# smartwatch.net
KiCad netlist of a schematic drawn in Altium Designer
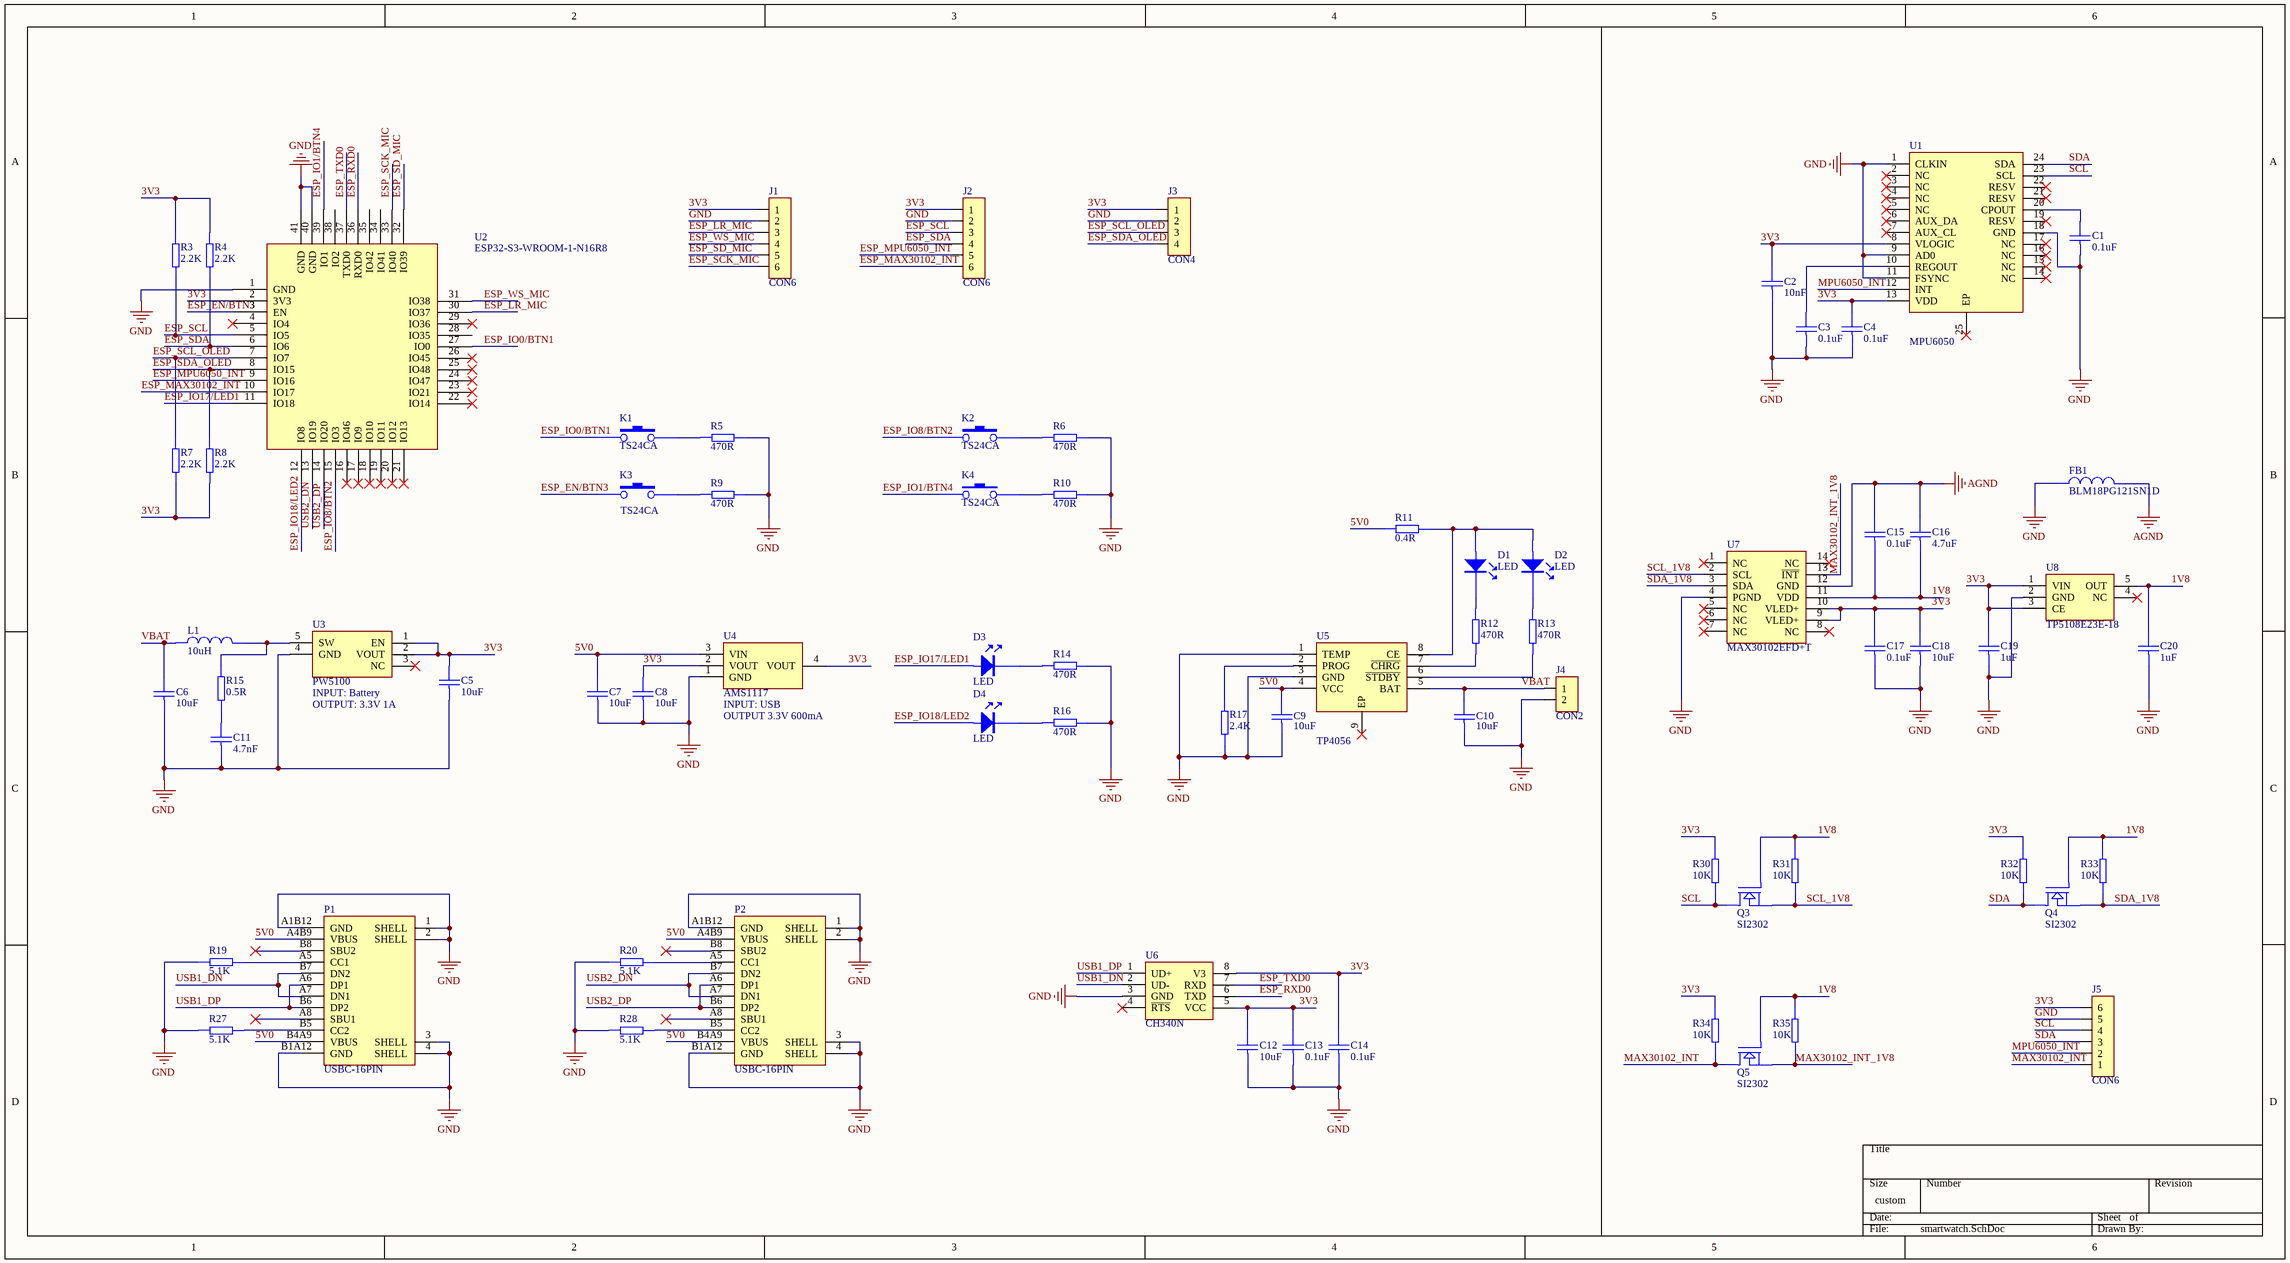
[diagram p0: smartwatch.SchDoc]

(export (version "E")
  (design (tool "Eeschema 10.0.6"))
  (components
    (comp (ref "C1")
      (value "0.1uF")
      (footprint "0603")
      (description "电容")
      (libsource (lib "smartwatch") (part "C"))
    )
    (comp (ref "C2")
      (value "10nF")
      (footprint "0603")
      (description "电容")
      (libsource (lib "smartwatch") (part "C"))
    )
    (comp (ref "C3")
      (value "0.1uF")
      (footprint "0603")
      (description "电容")
      (libsource (lib "smartwatch") (part "C"))
    )
    (comp (ref "C4")
      (value "0.1uF")
      (footprint "0603")
      (description "电容")
      (libsource (lib "smartwatch") (part "C"))
    )
    (comp (ref "C5")
      (value "10uF")
      (footprint "0603")
      (description "电容")
      (libsource (lib "smartwatch") (part "C"))
    )
    (comp (ref "C6")
      (value "10uF")
      (footprint "0603")
      (description "电容")
      (libsource (lib "smartwatch") (part "C"))
    )
    (comp (ref "C7")
      (value "10uF")
      (footprint "0603")
      (description "电容")
      (libsource (lib "smartwatch") (part "C"))
    )
    (comp (ref "C8")
      (value "10uF")
      (footprint "0603")
      (description "电容")
      (libsource (lib "smartwatch") (part "C"))
    )
    (comp (ref "C9")
      (value "10uF")
      (footprint "0603")
      (description "电容")
      (libsource (lib "smartwatch") (part "C"))
    )
    (comp (ref "C10")
      (value "10uF")
      (footprint "0603")
      (description "电容")
      (libsource (lib "smartwatch") (part "C"))
    )
    (comp (ref "C11")
      (value "4.7nF")
      (footprint "0603")
      (description "电容")
      (libsource (lib "smartwatch") (part "C"))
    )
    (comp (ref "C12")
      (value "10uF")
      (footprint "0603")
      (description "电容")
      (libsource (lib "smartwatch") (part "C"))
    )
    (comp (ref "C13")
      (value "0.1uF")
      (footprint "0603")
      (description "电容")
      (libsource (lib "smartwatch") (part "C"))
    )
    (comp (ref "C14")
      (value "0.1uF")
      (footprint "0603")
      (description "电容")
      (libsource (lib "smartwatch") (part "C"))
    )
    (comp (ref "C15")
      (value "0.1uF")
      (footprint "0603")
      (description "电容")
      (libsource (lib "smartwatch") (part "C"))
    )
    (comp (ref "C16")
      (value "4.7uF")
      (footprint "0603")
      (description "电容")
      (libsource (lib "smartwatch") (part "C"))
    )
    (comp (ref "C17")
      (value "0.1uF")
      (footprint "0603")
      (description "电容")
      (libsource (lib "smartwatch") (part "C"))
    )
    (comp (ref "C18")
      (value "10uF")
      (footprint "0603")
      (description "电容")
      (libsource (lib "smartwatch") (part "C"))
    )
    (comp (ref "C19")
      (value "1uF")
      (footprint "0603")
      (description "电容")
      (libsource (lib "smartwatch") (part "C"))
    )
    (comp (ref "C20")
      (value "1uF")
      (footprint "0603")
      (description "电容")
      (libsource (lib "smartwatch") (part "C"))
    )
    (comp (ref "D1") (value "LED") (footprint "LED0805-R-RD") (libsource (lib "smartwatch") (part "LED")))
    (comp (ref "D2") (value "LED") (footprint "LED0805-R-RD") (libsource (lib "smartwatch") (part "LED")))
    (comp (ref "D3") (value "LED") (footprint "LED0805-R-RD") (libsource (lib "smartwatch") (part "LED")))
    (comp (ref "D4") (value "LED") (footprint "LED0805-R-RD") (libsource (lib "smartwatch") (part "LED")))
    (comp (ref "FB1")
      (value "BLM18PG121SN1D")
      (footprint "0603")
      (description "磁珠")
      (libsource (lib "smartwatch") (part "FB"))
    )
    (comp (ref "J1")
      (value "CON6")
      (footprint "FPC-SMD_P0.50-6P_AFC01-S06FCA-00")
      (libsource (lib "smartwatch") (part "CON6"))
    )
    (comp (ref "J2")
      (value "CON6")
      (footprint "FPC-SMD_P0.50-6P_AFC01-S06FCA-00")
      (libsource (lib "smartwatch") (part "CON6"))
    )
    (comp (ref "J3")
      (value "CON4")
      (footprint "HDR2.54-M-LI-4P")
      (libsource (lib "smartwatch") (part "CON4"))
    )
    (comp (ref "J4") (value "CON2") (footprint "SIP-1.25-2P") (libsource (lib "smartwatch") (part "CON2")))
    (comp (ref "J5")
      (value "CON6")
      (footprint "FPC-SMD_P0.50-6P_AFC01-S06FCA-00")
      (libsource (lib "") (part "CON6_1"))
    )
    (comp (ref "K1")
      (value "TS24CA")
      (footprint "SW-SMD_TS24CA")
      (description "4.55*1.8*3.5mm 卧贴 轻触开关")
      (libsource (lib "smartwatch") (part "TS24CA"))
    )
    (comp (ref "K2")
      (value "TS24CA")
      (footprint "SW-SMD_TS24CA")
      (description "4.55*1.8*3.5mm 卧贴 轻触开关")
      (libsource (lib "smartwatch") (part "TS24CA"))
    )
    (comp (ref "K3")
      (value "TS24CA")
      (footprint "SW-SMD_TS24CA")
      (description "4.55*1.8*3.5mm 卧贴 轻触开关")
      (libsource (lib "smartwatch") (part "TS24CA"))
    )
    (comp (ref "K4")
      (value "TS24CA")
      (footprint "SW-SMD_TS24CA")
      (description "4.55*1.8*3.5mm 卧贴 轻触开关")
      (libsource (lib "smartwatch") (part "TS24CA"))
    )
    (comp (ref "L1")
      (value "10uH")
      (footprint "IND-SMD_L5.4-W5.2_FXL0530")
      (description "电感")
      (libsource (lib "smartwatch") (part "L"))
    )
    (comp (ref "P1")
      (value "USBC-16PIN")
      (footprint "USB-C-SMD_G-SWITCH_GT-USB-7010ASV")
      (description "USB Type-C母座 16PIN 卧贴")
      (libsource (lib "smartwatch") (part "USBC-16PIN"))
    )
    (comp (ref "P2")
      (value "USBC-16PIN")
      (footprint "USB-C-SMD_G-SWITCH_GT-USB-7010ASV")
      (description "USB Type-C母座 16PIN 卧贴")
      (libsource (lib "smartwatch") (part "USBC-16PIN"))
    )
    (comp (ref "Q3")
      (value "SI2302")
      (footprint "SOT-23-3_L2.9-W1.3-P1.90-LS2.4-BR")
      (libsource (lib "smartwatch") (part "MOSFET N"))
    )
    (comp (ref "Q4")
      (value "SI2302")
      (footprint "SOT-23-3_L2.9-W1.3-P1.90-LS2.4-BR")
      (libsource (lib "smartwatch") (part "MOSFET N"))
    )
    (comp (ref "Q5")
      (value "SI2302")
      (footprint "SOT-23-3_L2.9-W1.3-P1.90-LS2.4-BR")
      (libsource (lib "smartwatch") (part "MOSFET N"))
    )
    (comp (ref "R3")
      (value "2.2K")
      (footprint "0603")
      (description "电阻")
      (libsource (lib "smartwatch") (part "R"))
    )
    (comp (ref "R4")
      (value "2.2K")
      (footprint "0603")
      (description "电阻")
      (libsource (lib "smartwatch") (part "R"))
    )
    (comp (ref "R5")
      (value "470R")
      (footprint "0603")
      (description "电阻")
      (libsource (lib "smartwatch") (part "R"))
    )
    (comp (ref "R6")
      (value "470R")
      (footprint "0603")
      (description "电阻")
      (libsource (lib "smartwatch") (part "R"))
    )
    (comp (ref "R7")
      (value "2.2K")
      (footprint "0603")
      (description "电阻")
      (libsource (lib "smartwatch") (part "R"))
    )
    (comp (ref "R8")
      (value "2.2K")
      (footprint "0603")
      (description "电阻")
      (libsource (lib "smartwatch") (part "R"))
    )
    (comp (ref "R9")
      (value "470R")
      (footprint "0603")
      (description "电阻")
      (libsource (lib "smartwatch") (part "R"))
    )
    (comp (ref "R10")
      (value "470R")
      (footprint "0603")
      (description "电阻")
      (libsource (lib "smartwatch") (part "R"))
    )
    (comp (ref "R11")
      (value "0.4R")
      (footprint "2512")
      (description "电阻")
      (libsource (lib "smartwatch") (part "R"))
    )
    (comp (ref "R12")
      (value "470R")
      (footprint "0603")
      (description "电阻")
      (libsource (lib "smartwatch") (part "R"))
    )
    (comp (ref "R13")
      (value "470R")
      (footprint "0603")
      (description "电阻")
      (libsource (lib "smartwatch") (part "R"))
    )
    (comp (ref "R14")
      (value "470R")
      (footprint "0603")
      (description "电阻")
      (libsource (lib "smartwatch") (part "R"))
    )
    (comp (ref "R15")
      (value "0.5R")
      (footprint "0603")
      (description "电阻")
      (libsource (lib "smartwatch") (part "R"))
    )
    (comp (ref "R16")
      (value "470R")
      (footprint "0603")
      (description "电阻")
      (libsource (lib "smartwatch") (part "R"))
    )
    (comp (ref "R17")
      (value "2.4K")
      (footprint "0603")
      (description "电阻")
      (libsource (lib "smartwatch") (part "R"))
    )
    (comp (ref "R19")
      (value "5.1K")
      (footprint "0603")
      (description "电阻")
      (libsource (lib "smartwatch") (part "R"))
    )
    (comp (ref "R20")
      (value "5.1K")
      (footprint "0603")
      (description "电阻")
      (libsource (lib "smartwatch") (part "R"))
    )
    (comp (ref "R27")
      (value "5.1K")
      (footprint "0603")
      (description "电阻")
      (libsource (lib "smartwatch") (part "R"))
    )
    (comp (ref "R28")
      (value "5.1K")
      (footprint "0603")
      (description "电阻")
      (libsource (lib "smartwatch") (part "R"))
    )
    (comp (ref "R30")
      (value "10K")
      (footprint "0603")
      (description "电阻")
      (libsource (lib "smartwatch") (part "R"))
    )
    (comp (ref "R31")
      (value "10K")
      (footprint "0603")
      (description "电阻")
      (libsource (lib "smartwatch") (part "R"))
    )
    (comp (ref "R32")
      (value "10K")
      (footprint "0603")
      (description "电阻")
      (libsource (lib "smartwatch") (part "R"))
    )
    (comp (ref "R33")
      (value "10K")
      (footprint "0603")
      (description "电阻")
      (libsource (lib "smartwatch") (part "R"))
    )
    (comp (ref "R34")
      (value "10K")
      (footprint "0603")
      (description "电阻")
      (libsource (lib "smartwatch") (part "R"))
    )
    (comp (ref "R35")
      (value "10K")
      (footprint "0603")
      (description "电阻")
      (libsource (lib "smartwatch") (part "R"))
    )
    (comp (ref "U1")
      (value "MPU6050")
      (footprint "QFN-24_L4.0-W4.0-P0.50-BL-EP2.7")
      (description "三轴加速度计和三轴陀螺仪，工作电压：2.375V~3.46V")
      (libsource (lib "smartwatch") (part "MPU6050"))
    )
    (comp (ref "U2")
      (value "ESP32-S3-WROOM-1-N16R8")
      (footprint "WIRELM-SMD_ESP32-S3-WROOM-1_reduced")
      (description "通用型Wi-Fi+低功耗蓝牙MCU模组")
      (libsource (lib "smartwatch") (part "ESP32-S3-WROOM-1-N16R8"))
    )
    (comp (ref "U3")
      (value "PW5100")
      (footprint "SOT95P280X125-5N")
      (description "DC-DC")
      (libsource (lib "smartwatch") (part "PW5100"))
    )
    (comp (ref "U4")
      (value "AMS1117")
      (footprint "SOT223")
      (description "LDO 线性稳压器")
      (libsource (lib "smartwatch") (part "AMS1117"))
    )
    (comp (ref "U5")
      (value "TP4056")
      (footprint "ESOP-8_L4.9-W3.9-P1.27-LS6.0-BL-EP")
      (description "1A线性锂离子电池充电器")
      (libsource (lib "smartwatch") (part "TP4056"))
    )
    (comp (ref "U6")
      (value "CH340N")
      (footprint "SOP-8_L4.9-W3.9-P1.27-LS6.0-BL")
      (description "USB2.0芯片CH340N")
      (libsource (lib "smartwatch") (part "CH340N"))
    )
    (comp (ref "U7")
      (value "MAX30102EFD+T")
      (footprint "OESIP-14_L5.6-W3.3-P0.80-TL")
      (description "高灵敏度脉搏血氧仪和心率传感器")
      (libsource (lib "smartwatch") (part "MAX30102EFD+T"))
    )
    (comp (ref "U8")
      (value "TP5108E23E-18")
      (footprint "SOT-23-5_L3.0-W1.7-P0.95-LS2.8-BL")
      (description "LDO 输出1.8V 500mA")
      (libsource (lib "smartwatch") (part "TP5108E23E-18"))
    )
  )
  (nets
    (net (code "1") (name "/1V8") (class "Default")
      (node (ref "C15") (pin "1") (pinfunction "1_1") (pintype "passive"))
      (node (ref "C16") (pin "1") (pinfunction "1_1") (pintype "passive"))
      (node (ref "C20") (pin "2") (pinfunction "2_2") (pintype "passive"))
      (node (ref "Q3") (pin "1") (pinfunction "G_1") (pintype "passive"))
      (node (ref "Q4") (pin "1") (pinfunction "G_1") (pintype "passive"))
      (node (ref "Q5") (pin "1") (pinfunction "G_1") (pintype "passive"))
      (node (ref "R31") (pin "2") (pinfunction "2_2") (pintype "passive"))
      (node (ref "R33") (pin "2") (pinfunction "2_2") (pintype "passive"))
      (node (ref "R35") (pin "2") (pinfunction "2_2") (pintype "passive"))
      (node (ref "U7") (pin "11") (pinfunction "VDD_11") (pintype "passive"))
      (node (ref "U8") (pin "5") (pinfunction "OUT_5") (pintype "passive"))
    )
    (net (code "2") (name "/3V3") (class "Default")
      (node (ref "C12") (pin "2") (pinfunction "2_2") (pintype "passive"))
      (node (ref "C13") (pin "2") (pinfunction "2_2") (pintype "passive"))
      (node (ref "C14") (pin "2") (pinfunction "2_2") (pintype "passive"))
      (node (ref "C17") (pin "2") (pinfunction "2_2") (pintype "passive"))
      (node (ref "C18") (pin "2") (pinfunction "2_2") (pintype "passive"))
      (node (ref "C19") (pin "2") (pinfunction "2_2") (pintype "passive"))
      (node (ref "C2") (pin "2") (pinfunction "2_2") (pintype "passive"))
      (node (ref "C4") (pin "2") (pinfunction "2_2") (pintype "passive"))
      (node (ref "C5") (pin "2") (pinfunction "2_2") (pintype "passive"))
      (node (ref "C8") (pin "2") (pinfunction "2_2") (pintype "passive"))
      (node (ref "J1") (pin "1") (pinfunction "1_1") (pintype "passive"))
      (node (ref "J2") (pin "1") (pinfunction "1_1") (pintype "passive"))
      (node (ref "J3") (pin "1") (pinfunction "1_1") (pintype "passive"))
      (node (ref "J5") (pin "6") (pinfunction "6_6") (pintype "passive"))
      (node (ref "R3") (pin "2") (pinfunction "2_2") (pintype "passive"))
      (node (ref "R30") (pin "2") (pinfunction "2_2") (pintype "passive"))
      (node (ref "R32") (pin "2") (pinfunction "2_2") (pintype "passive"))
      (node (ref "R34") (pin "2") (pinfunction "2_2") (pintype "passive"))
      (node (ref "R4") (pin "2") (pinfunction "2_2") (pintype "passive"))
      (node (ref "R7") (pin "1") (pinfunction "1_1") (pintype "passive"))
      (node (ref "R8") (pin "1") (pinfunction "1_1") (pintype "passive"))
      (node (ref "U1") (pin "13") (pinfunction "VDD_13") (pintype "passive"))
      (node (ref "U1") (pin "8") (pinfunction "VLOGIC_8") (pintype "passive"))
      (node (ref "U2") (pin "2") (pinfunction "3V3_2") (pintype "passive"))
      (node (ref "U3") (pin "1") (pinfunction "EN_1") (pintype "passive"))
      (node (ref "U3") (pin "2") (pinfunction "VOUT_2") (pintype "passive"))
      (node (ref "U4") (pin "2") (pinfunction "VOUT_2") (pintype "passive"))
      (node (ref "U4") (pin "4") (pinfunction "VOUT_4") (pintype "passive"))
      (node (ref "U6") (pin "5") (pinfunction "VCC_5") (pintype "passive"))
      (node (ref "U6") (pin "8") (pinfunction "V3_8") (pintype "passive"))
      (node (ref "U7") (pin "10") (pinfunction "VLED+_10") (pintype "passive"))
      (node (ref "U7") (pin "9") (pinfunction "VLED+_9") (pintype "passive"))
      (node (ref "U8") (pin "1") (pinfunction "VIN_1") (pintype "passive"))
      (node (ref "U8") (pin "3") (pinfunction "CE_3") (pintype "passive"))
    )
    (net (code "3") (name "/5V0") (class "Default")
      (node (ref "C7") (pin "2") (pinfunction "2_2") (pintype "passive"))
      (node (ref "C9") (pin "2") (pinfunction "2_2") (pintype "passive"))
      (node (ref "P1") (pin "A4B9") (pinfunction "VBUS_A4B9") (pintype "passive"))
      (node (ref "P1") (pin "B4A9") (pinfunction "VBUS_B4A9") (pintype "passive"))
      (node (ref "P2") (pin "A4B9") (pinfunction "VBUS_A4B9") (pintype "passive"))
      (node (ref "P2") (pin "B4A9") (pinfunction "VBUS_B4A9") (pintype "passive"))
      (node (ref "R11") (pin "2") (pinfunction "2_2") (pintype "passive"))
      (node (ref "U4") (pin "3") (pinfunction "VIN_3") (pintype "passive"))
      (node (ref "U5") (pin "4") (pinfunction "VCC_4") (pintype "passive"))
    )
    (net (code "4") (name "/ESP_EN{slash}BTN3") (class "Default")
      (node (ref "K3") (pin "1") (pinfunction "1_1") (pintype "passive"))
      (node (ref "U2") (pin "3") (pinfunction "EN_3") (pintype "passive"))
    )
    (net (code "5") (name "/ESP_IO0{slash}BTN1") (class "Default")
      (node (ref "K1") (pin "1") (pinfunction "1_1") (pintype "passive"))
      (node (ref "U2") (pin "27") (pinfunction "IO0_27") (pintype "passive"))
    )
    (net (code "6") (name "/ESP_IO1{slash}BTN4") (class "Default")
      (node (ref "K4") (pin "2") (pinfunction "2_2") (pintype "passive"))
      (node (ref "U2") (pin "39") (pinfunction "IO1_39") (pintype "passive"))
    )
    (net (code "7") (name "/ESP_IO8{slash}BTN2") (class "Default")
      (node (ref "K2") (pin "1") (pinfunction "1_1") (pintype "passive"))
      (node (ref "U2") (pin "15") (pinfunction "IO3_15") (pintype "passive"))
    )
    (net (code "8") (name "/ESP_IO17{slash}LED1") (class "Default")
      (node (ref "D3") (pin "1") (pinfunction "1_1") (pintype "passive"))
      (node (ref "U2") (pin "11") (pinfunction "IO18_11") (pintype "passive"))
    )
    (net (code "9") (name "/ESP_IO18{slash}LED2") (class "Default")
      (node (ref "D4") (pin "1") (pinfunction "1_1") (pintype "passive"))
      (node (ref "U2") (pin "12") (pinfunction "IO8_12") (pintype "passive"))
    )
    (net (code "10") (name "/ESP_LR_MIC") (class "Default")
      (node (ref "J1") (pin "3") (pinfunction "3_3") (pintype "passive"))
      (node (ref "U2") (pin "30") (pinfunction "IO37_30") (pintype "passive"))
    )
    (net (code "11") (name "/ESP_MAX30102_INT") (class "Default")
      (node (ref "J2") (pin "6") (pinfunction "6_6") (pintype "passive"))
      (node (ref "U2") (pin "10") (pinfunction "IO17_10") (pintype "passive"))
    )
    (net (code "12") (name "/ESP_MPU6050_INT") (class "Default")
      (node (ref "J2") (pin "5") (pinfunction "5_5") (pintype "passive"))
      (node (ref "U2") (pin "9") (pinfunction "IO16_9") (pintype "passive"))
    )
    (net (code "13") (name "/ESP_RXD0") (class "Default")
      (node (ref "U2") (pin "36") (pinfunction "RXD0_36") (pintype "passive"))
      (node (ref "U6") (pin "6") (pinfunction "TXD_6") (pintype "passive"))
    )
    (net (code "14") (name "/ESP_SCK_MIC") (class "Default")
      (node (ref "J1") (pin "6") (pinfunction "6_6") (pintype "passive"))
      (node (ref "U2") (pin "33") (pinfunction "IO40_33") (pintype "passive"))
    )
    (net (code "15") (name "/ESP_SCL") (class "Default")
      (node (ref "J2") (pin "3") (pinfunction "3_3") (pintype "passive"))
      (node (ref "R3") (pin "1") (pinfunction "1_1") (pintype "passive"))
      (node (ref "U2") (pin "5") (pinfunction "IO5_5") (pintype "passive"))
    )
    (net (code "16") (name "/ESP_SCL_OLED") (class "Default")
      (node (ref "J3") (pin "3") (pinfunction "3_3") (pintype "passive"))
      (node (ref "R7") (pin "2") (pinfunction "2_2") (pintype "passive"))
      (node (ref "U2") (pin "7") (pinfunction "IO7_7") (pintype "passive"))
    )
    (net (code "17") (name "/ESP_SDA") (class "Default")
      (node (ref "J2") (pin "4") (pinfunction "4_4") (pintype "passive"))
      (node (ref "R4") (pin "1") (pinfunction "1_1") (pintype "passive"))
      (node (ref "U2") (pin "6") (pinfunction "IO6_6") (pintype "passive"))
    )
    (net (code "18") (name "/ESP_SDA_OLED") (class "Default")
      (node (ref "J3") (pin "4") (pinfunction "4_4") (pintype "passive"))
      (node (ref "R8") (pin "2") (pinfunction "2_2") (pintype "passive"))
      (node (ref "U2") (pin "8") (pinfunction "IO15_8") (pintype "passive"))
    )
    (net (code "19") (name "/ESP_SD_MIC") (class "Default")
      (node (ref "J1") (pin "5") (pinfunction "5_5") (pintype "passive"))
      (node (ref "U2") (pin "32") (pinfunction "IO39_32") (pintype "passive"))
    )
    (net (code "20") (name "/ESP_TXD0") (class "Default")
      (node (ref "U2") (pin "37") (pinfunction "TXD0_37") (pintype "passive"))
      (node (ref "U6") (pin "7") (pinfunction "RXD_7") (pintype "passive"))
    )
    (net (code "21") (name "/ESP_WS_MIC") (class "Default")
      (node (ref "J1") (pin "4") (pinfunction "4_4") (pintype "passive"))
      (node (ref "U2") (pin "31") (pinfunction "IO38_31") (pintype "passive"))
    )
    (net (code "22") (name "/MAX30102_INT") (class "Default")
      (node (ref "J5") (pin "1") (pinfunction "1_1") (pintype "passive"))
      (node (ref "Q5") (pin "3") (pinfunction "D_3") (pintype "passive"))
      (node (ref "R34") (pin "1") (pinfunction "1_1") (pintype "passive"))
    )
    (net (code "23") (name "/MAX30102_INT_1V8") (class "Default")
      (node (ref "Q5") (pin "2") (pinfunction "S_2") (pintype "passive"))
      (node (ref "R35") (pin "1") (pinfunction "1_1") (pintype "passive"))
      (node (ref "U7") (pin "13") (pinfunction "~{INT}_13") (pintype "passive"))
    )
    (net (code "24") (name "/MPU6050_INT") (class "Default")
      (node (ref "J5") (pin "2") (pinfunction "2_2") (pintype "passive"))
      (node (ref "U1") (pin "12") (pinfunction "INT_12") (pintype "passive"))
    )
    (net (code "25") (name "/SCL") (class "Default")
      (node (ref "J5") (pin "4") (pinfunction "4_4") (pintype "passive"))
      (node (ref "Q3") (pin "3") (pinfunction "D_3") (pintype "passive"))
      (node (ref "R30") (pin "1") (pinfunction "1_1") (pintype "passive"))
      (node (ref "U1") (pin "23") (pinfunction "SCL_23") (pintype "passive"))
    )
    (net (code "26") (name "/SCL_1V8") (class "Default")
      (node (ref "Q3") (pin "2") (pinfunction "S_2") (pintype "passive"))
      (node (ref "R31") (pin "1") (pinfunction "1_1") (pintype "passive"))
      (node (ref "U7") (pin "2") (pinfunction "SCL_2") (pintype "passive"))
    )
    (net (code "27") (name "/SDA") (class "Default")
      (node (ref "J5") (pin "3") (pinfunction "3_3") (pintype "passive"))
      (node (ref "Q4") (pin "3") (pinfunction "D_3") (pintype "passive"))
      (node (ref "R32") (pin "1") (pinfunction "1_1") (pintype "passive"))
      (node (ref "U1") (pin "24") (pinfunction "SDA_24") (pintype "passive"))
    )
    (net (code "28") (name "/SDA_1V8") (class "Default")
      (node (ref "Q4") (pin "2") (pinfunction "S_2") (pintype "passive"))
      (node (ref "R33") (pin "1") (pinfunction "1_1") (pintype "passive"))
      (node (ref "U7") (pin "3") (pinfunction "SDA_3") (pintype "passive"))
    )
    (net (code "29") (name "/USB1_DN") (class "Default")
      (node (ref "P1") (pin "A7") (pinfunction "DN1_A7") (pintype "passive"))
      (node (ref "P1") (pin "B7") (pinfunction "DN2_B7") (pintype "passive"))
      (node (ref "U6") (pin "2") (pinfunction "UD-_2") (pintype "passive"))
    )
    (net (code "30") (name "/USB1_DP") (class "Default")
      (node (ref "P1") (pin "A6") (pinfunction "DP1_A6") (pintype "passive"))
      (node (ref "P1") (pin "B6") (pinfunction "DP2_B6") (pintype "passive"))
      (node (ref "U6") (pin "1") (pinfunction "UD+_1") (pintype "passive"))
    )
    (net (code "31") (name "/USB2_DN") (class "Default")
      (node (ref "P2") (pin "A7") (pinfunction "DN1_A7") (pintype "passive"))
      (node (ref "P2") (pin "B7") (pinfunction "DN2_B7") (pintype "passive"))
      (node (ref "U2") (pin "13") (pinfunction "IO19_13") (pintype "passive"))
    )
    (net (code "32") (name "/USB2_DP") (class "Default")
      (node (ref "P2") (pin "A6") (pinfunction "DP1_A6") (pintype "passive"))
      (node (ref "P2") (pin "B6") (pinfunction "DP2_B6") (pintype "passive"))
      (node (ref "U2") (pin "14") (pinfunction "IO20_14") (pintype "passive"))
    )
    (net (code "33") (name "/VBAT") (class "Default")
      (node (ref "C10") (pin "2") (pinfunction "2_2") (pintype "passive"))
      (node (ref "C6") (pin "2") (pinfunction "2_2") (pintype "passive"))
      (node (ref "J4") (pin "1") (pinfunction "1_1") (pintype "passive"))
      (node (ref "L1") (pin "1") (pinfunction "1_1") (pintype "passive"))
      (node (ref "U5") (pin "5") (pinfunction "BAT_5") (pintype "passive"))
    )
    (net (code "34") (name "AGND") (class "Default")
      (node (ref "C15") (pin "2") (pinfunction "2_2") (pintype "passive"))
      (node (ref "C16") (pin "2") (pinfunction "2_2") (pintype "passive"))
      (node (ref "FB1") (pin "2") (pinfunction "2_2") (pintype "passive"))
      (node (ref "U7") (pin "12") (pinfunction "GND_12") (pintype "passive"))
    )
    (net (code "35") (name "GND") (class "Default")
      (node (ref "C1") (pin "1") (pinfunction "1_1") (pintype "passive"))
      (node (ref "C10") (pin "1") (pinfunction "1_1") (pintype "passive"))
      (node (ref "C11") (pin "1") (pinfunction "1_1") (pintype "passive"))
      (node (ref "C12") (pin "1") (pinfunction "1_1") (pintype "passive"))
      (node (ref "C13") (pin "1") (pinfunction "1_1") (pintype "passive"))
      (node (ref "C14") (pin "1") (pinfunction "1_1") (pintype "passive"))
      (node (ref "C17") (pin "1") (pinfunction "1_1") (pintype "passive"))
      (node (ref "C18") (pin "1") (pinfunction "1_1") (pintype "passive"))
      (node (ref "C19") (pin "1") (pinfunction "1_1") (pintype "passive"))
      (node (ref "C2") (pin "1") (pinfunction "1_1") (pintype "passive"))
      (node (ref "C20") (pin "1") (pinfunction "1_1") (pintype "passive"))
      (node (ref "C3") (pin "1") (pinfunction "1_1") (pintype "passive"))
      (node (ref "C4") (pin "1") (pinfunction "1_1") (pintype "passive"))
      (node (ref "C5") (pin "1") (pinfunction "1_1") (pintype "passive"))
      (node (ref "C6") (pin "1") (pinfunction "1_1") (pintype "passive"))
      (node (ref "C7") (pin "1") (pinfunction "1_1") (pintype "passive"))
      (node (ref "C8") (pin "1") (pinfunction "1_1") (pintype "passive"))
      (node (ref "C9") (pin "1") (pinfunction "1_1") (pintype "passive"))
      (node (ref "FB1") (pin "1") (pinfunction "1_1") (pintype "passive"))
      (node (ref "J1") (pin "2") (pinfunction "2_2") (pintype "passive"))
      (node (ref "J2") (pin "2") (pinfunction "2_2") (pintype "passive"))
      (node (ref "J3") (pin "2") (pinfunction "2_2") (pintype "passive"))
      (node (ref "J4") (pin "2") (pinfunction "2_2") (pintype "passive"))
      (node (ref "J5") (pin "5") (pinfunction "5_5") (pintype "passive"))
      (node (ref "P1") (pin "1") (pinfunction "SHELL_1") (pintype "passive"))
      (node (ref "P1") (pin "2") (pinfunction "SHELL_2") (pintype "passive"))
      (node (ref "P1") (pin "3") (pinfunction "SHELL_3") (pintype "passive"))
      (node (ref "P1") (pin "4") (pinfunction "SHELL_4") (pintype "passive"))
      (node (ref "P1") (pin "A1B12") (pinfunction "GND_A1B12") (pintype "passive"))
      (node (ref "P1") (pin "B1A12") (pinfunction "GND_B1A12") (pintype "passive"))
      (node (ref "P2") (pin "1") (pinfunction "SHELL_1") (pintype "passive"))
      (node (ref "P2") (pin "2") (pinfunction "SHELL_2") (pintype "passive"))
      (node (ref "P2") (pin "3") (pinfunction "SHELL_3") (pintype "passive"))
      (node (ref "P2") (pin "4") (pinfunction "SHELL_4") (pintype "passive"))
      (node (ref "P2") (pin "A1B12") (pinfunction "GND_A1B12") (pintype "passive"))
      (node (ref "P2") (pin "B1A12") (pinfunction "GND_B1A12") (pintype "passive"))
      (node (ref "R10") (pin "2") (pinfunction "2_2") (pintype "passive"))
      (node (ref "R14") (pin "1") (pinfunction "1_1") (pintype "passive"))
      (node (ref "R16") (pin "1") (pinfunction "1_1") (pintype "passive"))
      (node (ref "R17") (pin "2") (pinfunction "2_2") (pintype "passive"))
      (node (ref "R19") (pin "1") (pinfunction "1_1") (pintype "passive"))
      (node (ref "R20") (pin "1") (pinfunction "1_1") (pintype "passive"))
      (node (ref "R27") (pin "1") (pinfunction "1_1") (pintype "passive"))
      (node (ref "R28") (pin "1") (pinfunction "1_1") (pintype "passive"))
      (node (ref "R5") (pin "2") (pinfunction "2_2") (pintype "passive"))
      (node (ref "R6") (pin "2") (pinfunction "2_2") (pintype "passive"))
      (node (ref "R9") (pin "2") (pinfunction "2_2") (pintype "passive"))
      (node (ref "U1") (pin "1") (pinfunction "CLKIN_1") (pintype "passive"))
      (node (ref "U1") (pin "11") (pinfunction "FSYNC_11") (pintype "passive"))
      (node (ref "U1") (pin "18") (pinfunction "GND_18") (pintype "passive"))
      (node (ref "U1") (pin "9") (pinfunction "AD0_9") (pintype "passive"))
      (node (ref "U2") (pin "1") (pinfunction "GND_1") (pintype "passive"))
      (node (ref "U2") (pin "40") (pinfunction "GND_40") (pintype "passive"))
      (node (ref "U2") (pin "41") (pinfunction "GND_41") (pintype "passive"))
      (node (ref "U3") (pin "4") (pinfunction "GND_4") (pintype "passive"))
      (node (ref "U4") (pin "1") (pinfunction "GND_1") (pintype "passive"))
      (node (ref "U5") (pin "1") (pinfunction "TEMP_1") (pintype "passive"))
      (node (ref "U5") (pin "3") (pinfunction "GND_3") (pintype "passive"))
      (node (ref "U6") (pin "3") (pinfunction "GND_3") (pintype "passive"))
      (node (ref "U7") (pin "4") (pinfunction "PGND_4") (pintype "passive"))
      (node (ref "U8") (pin "2") (pinfunction "GND_2") (pintype "passive"))
    )
    (net (code "36") (name "Net-(C11-Pad2)") (class "Default")
      (node (ref "C11") (pin "2") (pinfunction "2_2") (pintype "passive"))
      (node (ref "R15") (pin "1") (pinfunction "1_1") (pintype "passive"))
    )
    (net (code "37") (name "Net-(D1-Pad2)") (class "Default")
      (node (ref "D1") (pin "2") (pinfunction "2_2") (pintype "passive"))
      (node (ref "R12") (pin "2") (pinfunction "2_2") (pintype "passive"))
    )
    (net (code "38") (name "Net-(D2-Pad2)") (class "Default")
      (node (ref "D2") (pin "2") (pinfunction "2_2") (pintype "passive"))
      (node (ref "R13") (pin "2") (pinfunction "2_2") (pintype "passive"))
    )
    (net (code "39") (name "Net-(D3-Pad2)") (class "Default")
      (node (ref "D3") (pin "2") (pinfunction "2_2") (pintype "passive"))
      (node (ref "R14") (pin "2") (pinfunction "2_2") (pintype "passive"))
    )
    (net (code "40") (name "Net-(D4-Pad2)") (class "Default")
      (node (ref "D4") (pin "2") (pinfunction "2_2") (pintype "passive"))
      (node (ref "R16") (pin "2") (pinfunction "2_2") (pintype "passive"))
    )
    (net (code "41") (name "Net-(K1-Pad2)") (class "Default")
      (node (ref "K1") (pin "2") (pinfunction "2_2") (pintype "passive"))
      (node (ref "R5") (pin "1") (pinfunction "1_1") (pintype "passive"))
    )
    (net (code "42") (name "Net-(K2-Pad2)") (class "Default")
      (node (ref "K2") (pin "2") (pinfunction "2_2") (pintype "passive"))
      (node (ref "R6") (pin "1") (pinfunction "1_1") (pintype "passive"))
    )
    (net (code "43") (name "Net-(K3-Pad2)") (class "Default")
      (node (ref "K3") (pin "2") (pinfunction "2_2") (pintype "passive"))
      (node (ref "R9") (pin "1") (pinfunction "1_1") (pintype "passive"))
    )
    (net (code "44") (name "Net-(K4-Pad1)") (class "Default")
      (node (ref "K4") (pin "1") (pinfunction "1_1") (pintype "passive"))
      (node (ref "R10") (pin "1") (pinfunction "1_1") (pintype "passive"))
    )
    (net (code "45") (name "Net-(P1-CC1)") (class "Default")
      (node (ref "P1") (pin "A5") (pinfunction "CC1_A5") (pintype "passive"))
      (node (ref "R19") (pin "2") (pinfunction "2_2") (pintype "passive"))
    )
    (net (code "46") (name "Net-(P1-CC2)") (class "Default")
      (node (ref "P1") (pin "B5") (pinfunction "CC2_B5") (pintype "passive"))
      (node (ref "R27") (pin "2") (pinfunction "2_2") (pintype "passive"))
    )
    (net (code "47") (name "Net-(P2-CC1)") (class "Default")
      (node (ref "P2") (pin "A5") (pinfunction "CC1_A5") (pintype "passive"))
      (node (ref "R20") (pin "2") (pinfunction "2_2") (pintype "passive"))
    )
    (net (code "48") (name "Net-(P2-CC2)") (class "Default")
      (node (ref "P2") (pin "B5") (pinfunction "CC2_B5") (pintype "passive"))
      (node (ref "R28") (pin "2") (pinfunction "2_2") (pintype "passive"))
    )
    (net (code "49") (name "Net-(U1-CPOUT)") (class "Default")
      (node (ref "C1") (pin "2") (pinfunction "2_2") (pintype "passive"))
      (node (ref "U1") (pin "20") (pinfunction "CPOUT_20") (pintype "passive"))
    )
    (net (code "50") (name "Net-(U1-REGOUT)") (class "Default")
      (node (ref "C3") (pin "2") (pinfunction "2_2") (pintype "passive"))
      (node (ref "U1") (pin "10") (pinfunction "REGOUT_10") (pintype "passive"))
    )
    (net (code "51") (name "Net-(U3-SW)") (class "Default")
      (node (ref "L1") (pin "2") (pinfunction "2_2") (pintype "passive"))
      (node (ref "R15") (pin "2") (pinfunction "2_2") (pintype "passive"))
      (node (ref "U3") (pin "5") (pinfunction "SW_5") (pintype "passive"))
    )
    (net (code "52") (name "Net-(U5-CE)") (class "Default")
      (node (ref "D1") (pin "1") (pinfunction "1_1") (pintype "passive"))
      (node (ref "D2") (pin "1") (pinfunction "1_1") (pintype "passive"))
      (node (ref "R11") (pin "1") (pinfunction "1_1") (pintype "passive"))
      (node (ref "U5") (pin "8") (pinfunction "CE_8") (pintype "passive"))
    )
    (net (code "53") (name "Net-(U5-PROG)") (class "Default")
      (node (ref "R17") (pin "1") (pinfunction "1_1") (pintype "passive"))
      (node (ref "U5") (pin "2") (pinfunction "PROG_2") (pintype "passive"))
    )
    (net (code "54") (name "Net-(U5-~{CHRG})") (class "Default")
      (node (ref "R12") (pin "1") (pinfunction "1_1") (pintype "passive"))
      (node (ref "U5") (pin "7") (pinfunction "~{CHRG}_7") (pintype "passive"))
    )
    (net (code "55") (name "Net-(U5-~{STDBY})") (class "Default")
      (node (ref "R13") (pin "1") (pinfunction "1_1") (pintype "passive"))
      (node (ref "U5") (pin "6") (pinfunction "~{STDBY}_6") (pintype "passive"))
    )
    (net (code "56") (name "unconnected-(P1-SBU1-PadA8)") (class "Default")
      (node (ref "P1") (pin "A8") (pinfunction "SBU1_A8") (pintype "passive+no_connect"))
    )
    (net (code "57") (name "unconnected-(P1-SBU2-PadB8)") (class "Default")
      (node (ref "P1") (pin "B8") (pinfunction "SBU2_B8") (pintype "passive+no_connect"))
    )
    (net (code "58") (name "unconnected-(P2-SBU1-PadA8)") (class "Default")
      (node (ref "P2") (pin "A8") (pinfunction "SBU1_A8") (pintype "passive+no_connect"))
    )
    (net (code "59") (name "unconnected-(P2-SBU2-PadB8)") (class "Default")
      (node (ref "P2") (pin "B8") (pinfunction "SBU2_B8") (pintype "passive+no_connect"))
    )
    (net (code "60") (name "unconnected-(U1-AUX_CL-Pad7)") (class "Default")
      (node (ref "U1") (pin "7") (pinfunction "AUX_CL_7") (pintype "passive+no_connect"))
    )
    (net (code "61") (name "unconnected-(U1-AUX_DA-Pad6)") (class "Default")
      (node (ref "U1") (pin "6") (pinfunction "AUX_DA_6") (pintype "passive+no_connect"))
    )
    (net (code "62") (name "unconnected-(U1-EP-Pad25)") (class "Default")
      (node (ref "U1") (pin "25") (pinfunction "EP_25") (pintype "passive+no_connect"))
    )
    (net (code "63") (name "unconnected-(U1-NC-Pad2)") (class "Default")
      (node (ref "U1") (pin "2") (pinfunction "NC_2") (pintype "passive+no_connect"))
    )
    (net (code "64") (name "unconnected-(U1-NC-Pad3)") (class "Default")
      (node (ref "U1") (pin "3") (pinfunction "NC_3") (pintype "passive+no_connect"))
    )
    (net (code "65") (name "unconnected-(U1-NC-Pad4)") (class "Default")
      (node (ref "U1") (pin "4") (pinfunction "NC_4") (pintype "passive+no_connect"))
    )
    (net (code "66") (name "unconnected-(U1-NC-Pad5)") (class "Default")
      (node (ref "U1") (pin "5") (pinfunction "NC_5") (pintype "passive+no_connect"))
    )
    (net (code "67") (name "unconnected-(U1-NC-Pad14)") (class "Default")
      (node (ref "U1") (pin "14") (pinfunction "NC_14") (pintype "passive+no_connect"))
    )
    (net (code "68") (name "unconnected-(U1-NC-Pad15)") (class "Default")
      (node (ref "U1") (pin "15") (pinfunction "NC_15") (pintype "passive+no_connect"))
    )
    (net (code "69") (name "unconnected-(U1-NC-Pad16)") (class "Default")
      (node (ref "U1") (pin "16") (pinfunction "NC_16") (pintype "passive+no_connect"))
    )
    (net (code "70") (name "unconnected-(U1-NC-Pad17)") (class "Default")
      (node (ref "U1") (pin "17") (pinfunction "NC_17") (pintype "passive+no_connect"))
    )
    (net (code "71") (name "unconnected-(U1-RESV-Pad19)") (class "Default")
      (node (ref "U1") (pin "19") (pinfunction "RESV_19") (pintype "passive+no_connect"))
    )
    (net (code "72") (name "unconnected-(U1-RESV-Pad21)") (class "Default")
      (node (ref "U1") (pin "21") (pinfunction "RESV_21") (pintype "passive+no_connect"))
    )
    (net (code "73") (name "unconnected-(U1-RESV-Pad22)") (class "Default")
      (node (ref "U1") (pin "22") (pinfunction "RESV_22") (pintype "passive+no_connect"))
    )
    (net (code "74") (name "unconnected-(U2-IO2-Pad38)") (class "Default")
      (node (ref "U2") (pin "38") (pinfunction "IO2_38") (pintype "passive"))
    )
    (net (code "75") (name "unconnected-(U2-IO4-Pad4)") (class "Default")
      (node (ref "U2") (pin "4") (pinfunction "IO4_4") (pintype "passive+no_connect"))
    )
    (net (code "76") (name "unconnected-(U2-IO9-Pad17)") (class "Default")
      (node (ref "U2") (pin "17") (pinfunction "IO9_17") (pintype "passive+no_connect"))
    )
    (net (code "77") (name "unconnected-(U2-IO10-Pad18)") (class "Default")
      (node (ref "U2") (pin "18") (pinfunction "IO10_18") (pintype "passive+no_connect"))
    )
    (net (code "78") (name "unconnected-(U2-IO11-Pad19)") (class "Default")
      (node (ref "U2") (pin "19") (pinfunction "IO11_19") (pintype "passive+no_connect"))
    )
    (net (code "79") (name "unconnected-(U2-IO12-Pad20)") (class "Default")
      (node (ref "U2") (pin "20") (pinfunction "IO12_20") (pintype "passive+no_connect"))
    )
    (net (code "80") (name "unconnected-(U2-IO13-Pad21)") (class "Default")
      (node (ref "U2") (pin "21") (pinfunction "IO13_21") (pintype "passive+no_connect"))
    )
    (net (code "81") (name "unconnected-(U2-IO14-Pad22)") (class "Default")
      (node (ref "U2") (pin "22") (pinfunction "IO14_22") (pintype "passive+no_connect"))
    )
    (net (code "82") (name "unconnected-(U2-IO21-Pad23)") (class "Default")
      (node (ref "U2") (pin "23") (pinfunction "IO21_23") (pintype "passive+no_connect"))
    )
    (net (code "83") (name "unconnected-(U2-IO35-Pad28)") (class "Default")
      (node (ref "U2") (pin "28") (pinfunction "IO35_28") (pintype "passive"))
    )
    (net (code "84") (name "unconnected-(U2-IO36-Pad29)") (class "Default")
      (node (ref "U2") (pin "29") (pinfunction "IO36_29") (pintype "passive+no_connect"))
    )
    (net (code "85") (name "unconnected-(U2-IO41-Pad34)") (class "Default")
      (node (ref "U2") (pin "34") (pinfunction "IO41_34") (pintype "passive"))
    )
    (net (code "86") (name "unconnected-(U2-IO42-Pad35)") (class "Default")
      (node (ref "U2") (pin "35") (pinfunction "IO42_35") (pintype "passive"))
    )
    (net (code "87") (name "unconnected-(U2-IO45-Pad26)") (class "Default")
      (node (ref "U2") (pin "26") (pinfunction "IO45_26") (pintype "passive+no_connect"))
    )
    (net (code "88") (name "unconnected-(U2-IO46-Pad16)") (class "Default")
      (node (ref "U2") (pin "16") (pinfunction "IO46_16") (pintype "passive+no_connect"))
    )
    (net (code "89") (name "unconnected-(U2-IO47-Pad24)") (class "Default")
      (node (ref "U2") (pin "24") (pinfunction "IO47_24") (pintype "passive+no_connect"))
    )
    (net (code "90") (name "unconnected-(U2-IO48-Pad25)") (class "Default")
      (node (ref "U2") (pin "25") (pinfunction "IO48_25") (pintype "passive+no_connect"))
    )
    (net (code "91") (name "unconnected-(U3-NC-Pad3)") (class "Default")
      (node (ref "U3") (pin "3") (pinfunction "NC_3") (pintype "passive+no_connect"))
    )
    (net (code "92") (name "unconnected-(U5-EP-Pad9)") (class "Default")
      (node (ref "U5") (pin "9") (pinfunction "EP_9") (pintype "passive+no_connect"))
    )
    (net (code "93") (name "unconnected-(U6-~{RTS}-Pad4)") (class "Default")
      (node (ref "U6") (pin "4") (pinfunction "~{RTS}_4") (pintype "passive+no_connect"))
    )
    (net (code "94") (name "unconnected-(U7-NC-Pad1)") (class "Default")
      (node (ref "U7") (pin "1") (pinfunction "NC_1") (pintype "passive+no_connect"))
    )
    (net (code "95") (name "unconnected-(U7-NC-Pad5)") (class "Default")
      (node (ref "U7") (pin "5") (pinfunction "NC_5") (pintype "passive+no_connect"))
    )
    (net (code "96") (name "unconnected-(U7-NC-Pad6)") (class "Default")
      (node (ref "U7") (pin "6") (pinfunction "NC_6") (pintype "passive+no_connect"))
    )
    (net (code "97") (name "unconnected-(U7-NC-Pad7)") (class "Default")
      (node (ref "U7") (pin "7") (pinfunction "NC_7") (pintype "passive+no_connect"))
    )
    (net (code "98") (name "unconnected-(U7-NC-Pad8)") (class "Default")
      (node (ref "U7") (pin "8") (pinfunction "NC_8") (pintype "passive+no_connect"))
    )
    (net (code "99") (name "unconnected-(U7-NC-Pad14)") (class "Default")
      (node (ref "U7") (pin "14") (pinfunction "NC_14") (pintype "passive+no_connect"))
    )
    (net (code "100") (name "unconnected-(U8-NC-Pad4)") (class "Default")
      (node (ref "U8") (pin "4") (pinfunction "NC_4") (pintype "passive+no_connect"))
    )
  )
)
